# main.net
KiCad netlist of a schematic drawn in EAGLE
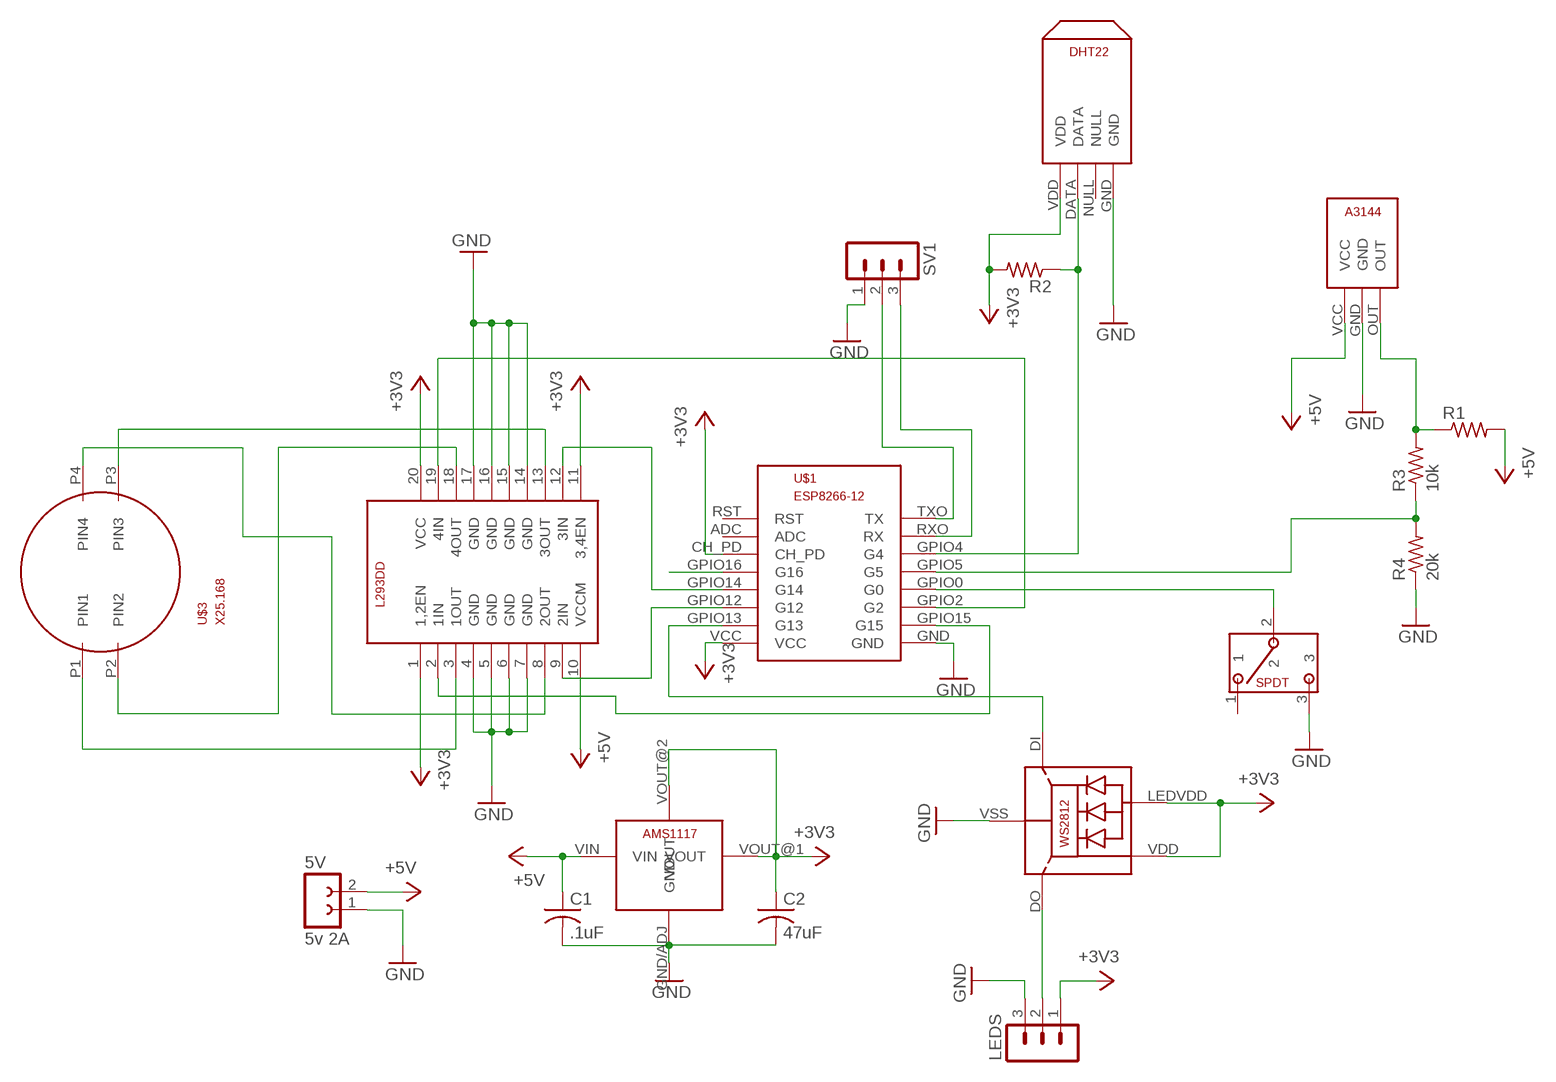
[diagram p0: schematic, sheet 1]

(export (version "E")
  (design (tool "Eeschema 10.0.6"))
  (components
    (comp (ref "5V")
      (value "5v 2A")
      (footprint "eagle-import:FE02-1")
      (libsource (lib "eagle-import") (part "FE02-1"))
    )
    (comp (ref "C1")
      (value ".1uF")
      (footprint "eagle-import:C0805")
      (libsource (lib "eagle-import") (part "C-USC0805"))
    )
    (comp (ref "C2")
      (value "47uF")
      (footprint "eagle-import:C0805")
      (libsource (lib "eagle-import") (part "C-USC0805"))
    )
    (comp (ref "LED1")
      (value "WS2812")
      (footprint "eagle-import:WS2812")
      (libsource (lib "eagle-import") (part "WS2812"))
    )
    (comp (ref "LEDS")
      (value "MA03-1")
      (footprint "eagle-import:MA03-1")
      (libsource (lib "eagle-import") (part "MA03-1"))
    )
    (comp (ref "R1")
      (value "R-US_R0805")
      (footprint "eagle-import:R0805")
      (libsource (lib "eagle-import") (part "R-US_R0805"))
    )
    (comp (ref "R2")
      (value "R-US_R0805")
      (footprint "eagle-import:R0805")
      (libsource (lib "eagle-import") (part "R-US_R0805"))
    )
    (comp (ref "R3")
      (value "10k")
      (footprint "eagle-import:R0805")
      (libsource (lib "eagle-import") (part "R-US_R0805"))
    )
    (comp (ref "R4")
      (value "20k")
      (footprint "eagle-import:R0805")
      (libsource (lib "eagle-import") (part "R-US_R0805"))
    )
    (comp (ref "SV1")
      (value "MA03-1")
      (footprint "eagle-import:MA03-1")
      (libsource (lib "eagle-import") (part "MA03-1"))
    )
    (comp (ref "U$1")
      (value "ESP12ESP12")
      (footprint "eagle-import:ESP12")
      (libsource (lib "eagle-import") (part "ESP12ESP12"))
    )
    (comp (ref "U$3")
      (value "X25.168X25.SMT")
      (footprint "eagle-import:X25-SMT")
      (libsource (lib "eagle-import") (part "X25.168X25.SMT"))
    )
    (comp (ref "U$4")
      (value "A3144")
      (footprint "eagle-import:A3144")
      (libsource (lib "eagle-import") (part "A3144"))
    )
    (comp (ref "U$5")
      (value "DH22FLAT")
      (footprint "eagle-import:DH22FLAT")
      (libsource (lib "eagle-import") (part "DH22FLAT"))
    )
    (comp (ref "U$6")
      (value "AMS11173.3V")
      (footprint "eagle-import:AMS1117")
      (libsource (lib "eagle-import") (part "AMS11173.3V"))
    )
    (comp (ref "U$7")
      (value "SMT-SPDT")
      (footprint "eagle-import:SPDT")
      (libsource (lib "eagle-import") (part "SMT-SPDT"))
    )
    (comp (ref "U$8")
      (value "L293DD")
      (footprint "eagle-import:SO20")
      (libsource (lib "eagle-import") (part "L293DD"))
    )
  )
  (nets
    (net (code "1") (name "+3V3") (class "Default")
      (node (ref "C2") (pin "1") (pinfunction "1_1") (pintype "passive"))
      (node (ref "LED1") (pin "LEDVDD") (pinfunction "LEDVDD_LEDVDD") (pintype "power_in"))
      (node (ref "LED1") (pin "VDD") (pinfunction "VDD_VDD") (pintype "power_in"))
      (node (ref "LEDS") (pin "1") (pinfunction "1_1") (pintype "passive"))
      (node (ref "R2") (pin "2") (pinfunction "2_2") (pintype "passive"))
      (node (ref "U$1") (pin "CH_PD") (pinfunction "CH_PD_CH_PD") (pintype "bidirectional"))
      (node (ref "U$1") (pin "VCC") (pinfunction "VCC_VCC") (pintype "bidirectional"))
      (node (ref "U$5") (pin "VDD") (pinfunction "VDD_VDD") (pintype "bidirectional"))
      (node (ref "U$6") (pin "VOUT@1") (pinfunction "VOUT_VOUT@1") (pintype "bidirectional"))
      (node (ref "U$6") (pin "VOUT@2") (pinfunction "VOUT_VOUT@2") (pintype "bidirectional"))
      (node (ref "U$8") (pin "1") (pinfunction "1,2EN_1") (pintype "bidirectional"))
      (node (ref "U$8") (pin "11") (pinfunction "3,4EN_11") (pintype "bidirectional"))
      (node (ref "U$8") (pin "20") (pinfunction "VCC_20") (pintype "bidirectional"))
    )
    (net (code "2") (name "+5V") (class "Default")
      (node (ref "5V") (pin "2") (pinfunction "2_2") (pintype "passive"))
      (node (ref "C1") (pin "1") (pinfunction "1_1") (pintype "passive"))
      (node (ref "R1") (pin "2") (pinfunction "2_2") (pintype "passive"))
      (node (ref "U$4") (pin "VCC") (pinfunction "VCC_VCC") (pintype "bidirectional"))
      (node (ref "U$6") (pin "VIN") (pinfunction "VIN_VIN") (pintype "bidirectional"))
      (node (ref "U$8") (pin "10") (pinfunction "VCCM_10") (pintype "bidirectional"))
    )
    (net (code "3") (name "GND") (class "Default")
      (node (ref "5V") (pin "1") (pinfunction "1_1") (pintype "passive"))
      (node (ref "C1") (pin "2") (pinfunction "2_2") (pintype "passive"))
      (node (ref "C2") (pin "2") (pinfunction "2_2") (pintype "passive"))
      (node (ref "LED1") (pin "VSS") (pinfunction "GND_VSS") (pintype "power_in"))
      (node (ref "LEDS") (pin "3") (pinfunction "3_3") (pintype "passive"))
      (node (ref "R4") (pin "1") (pinfunction "1_1") (pintype "passive"))
      (node (ref "SV1") (pin "1") (pinfunction "1_1") (pintype "passive"))
      (node (ref "U$1") (pin "GND") (pinfunction "GND_GND") (pintype "bidirectional"))
      (node (ref "U$4") (pin "GND") (pinfunction "GND_GND") (pintype "bidirectional"))
      (node (ref "U$5") (pin "GND") (pinfunction "GND_GND") (pintype "bidirectional"))
      (node (ref "U$6") (pin "GND/ADJ") (pinfunction "GND_GND/ADJ") (pintype "bidirectional"))
      (node (ref "U$7") (pin "3") (pinfunction "3_3") (pintype "bidirectional"))
      (node (ref "U$8") (pin "14") (pinfunction "GND_14") (pintype "bidirectional"))
      (node (ref "U$8") (pin "15") (pinfunction "GND_15") (pintype "bidirectional"))
      (node (ref "U$8") (pin "16") (pinfunction "GND_16") (pintype "bidirectional"))
      (node (ref "U$8") (pin "17") (pinfunction "GND_17") (pintype "bidirectional"))
      (node (ref "U$8") (pin "4") (pinfunction "GND_4") (pintype "bidirectional"))
      (node (ref "U$8") (pin "5") (pinfunction "GND_5") (pintype "bidirectional"))
      (node (ref "U$8") (pin "6") (pinfunction "GND_6") (pintype "bidirectional"))
      (node (ref "U$8") (pin "7") (pinfunction "GND_7") (pintype "bidirectional"))
    )
    (net (code "4") (name "Net-(LED1-PadDO)") (class "Default")
      (node (ref "LED1") (pin "DO") (pinfunction "DO_DO") (pintype "output"))
      (node (ref "LEDS") (pin "2") (pinfunction "2_2") (pintype "passive"))
    )
    (net (code "5") (name "Net-(R1-Pad1)") (class "Default")
      (node (ref "R1") (pin "1") (pinfunction "1_1") (pintype "passive"))
      (node (ref "R3") (pin "2") (pinfunction "2_2") (pintype "passive"))
      (node (ref "U$4") (pin "OUT") (pinfunction "OUT_OUT") (pintype "bidirectional"))
    )
    (net (code "6") (name "Net-(U$1-G0)") (class "Default")
      (node (ref "U$1") (pin "GPIO0") (pinfunction "G0_GPIO0") (pintype "bidirectional"))
      (node (ref "U$7") (pin "2") (pinfunction "2_2") (pintype "bidirectional"))
    )
    (net (code "7") (name "Net-(U$1-G2)") (class "Default")
      (node (ref "U$1") (pin "GPIO2") (pinfunction "G2_GPIO2") (pintype "bidirectional"))
      (node (ref "U$8") (pin "19") (pinfunction "4IN_19") (pintype "bidirectional"))
    )
    (net (code "8") (name "Net-(U$1-G4)") (class "Default")
      (node (ref "R2") (pin "1") (pinfunction "1_1") (pintype "passive"))
      (node (ref "U$1") (pin "GPIO4") (pinfunction "G4_GPIO4") (pintype "bidirectional"))
      (node (ref "U$5") (pin "DATA") (pinfunction "DATA_DATA") (pintype "bidirectional"))
    )
    (net (code "9") (name "Net-(U$1-G5)") (class "Default")
      (node (ref "R3") (pin "1") (pinfunction "1_1") (pintype "passive"))
      (node (ref "R4") (pin "2") (pinfunction "2_2") (pintype "passive"))
      (node (ref "U$1") (pin "GPIO5") (pinfunction "G5_GPIO5") (pintype "bidirectional"))
    )
    (net (code "10") (name "Net-(U$1-G12)") (class "Default")
      (node (ref "U$1") (pin "GPIO12") (pinfunction "G12_GPIO12") (pintype "bidirectional"))
      (node (ref "U$8") (pin "9") (pinfunction "2IN_9") (pintype "bidirectional"))
    )
    (net (code "11") (name "Net-(U$1-G13)") (class "Default")
      (node (ref "LED1") (pin "DI") (pinfunction "DI_DI") (pintype "input"))
      (node (ref "U$1") (pin "GPIO13") (pinfunction "G13_GPIO13") (pintype "bidirectional"))
    )
    (net (code "12") (name "Net-(U$1-G14)") (class "Default")
      (node (ref "U$1") (pin "GPIO14") (pinfunction "G14_GPIO14") (pintype "bidirectional"))
      (node (ref "U$8") (pin "12") (pinfunction "3IN_12") (pintype "bidirectional"))
    )
    (net (code "13") (name "Net-(U$1-G15)") (class "Default")
      (node (ref "U$1") (pin "GPIO15") (pinfunction "G15_GPIO15") (pintype "bidirectional"))
      (node (ref "U$8") (pin "2") (pinfunction "1IN_2") (pintype "bidirectional"))
    )
    (net (code "14") (name "Net-(U$1-RX)") (class "Default")
      (node (ref "SV1") (pin "3") (pinfunction "3_3") (pintype "passive"))
      (node (ref "U$1") (pin "RXO") (pinfunction "RX_RXO") (pintype "bidirectional"))
    )
    (net (code "15") (name "Net-(U$1-TX)") (class "Default")
      (node (ref "SV1") (pin "2") (pinfunction "2_2") (pintype "passive"))
      (node (ref "U$1") (pin "TXO") (pinfunction "TX_TXO") (pintype "bidirectional"))
    )
    (net (code "16") (name "Net-(U$3-PIN1)") (class "Default")
      (node (ref "U$3") (pin "P1") (pinfunction "PIN1_P1") (pintype "bidirectional"))
      (node (ref "U$8") (pin "3") (pinfunction "1OUT_3") (pintype "bidirectional"))
    )
    (net (code "17") (name "Net-(U$3-PIN2)") (class "Default")
      (node (ref "U$3") (pin "P2") (pinfunction "PIN2_P2") (pintype "bidirectional"))
      (node (ref "U$8") (pin "18") (pinfunction "4OUT_18") (pintype "bidirectional"))
    )
    (net (code "18") (name "Net-(U$3-PIN3)") (class "Default")
      (node (ref "U$3") (pin "P3") (pinfunction "PIN3_P3") (pintype "bidirectional"))
      (node (ref "U$8") (pin "13") (pinfunction "3OUT_13") (pintype "bidirectional"))
    )
    (net (code "19") (name "Net-(U$3-PIN4)") (class "Default")
      (node (ref "U$3") (pin "P4") (pinfunction "PIN4_P4") (pintype "bidirectional"))
      (node (ref "U$8") (pin "8") (pinfunction "2OUT_8") (pintype "bidirectional"))
    )
    (net (code "20") (name "unconnected-(U$1-G16-PadGPIO16)") (class "Default")
      (node (ref "U$1") (pin "GPIO16") (pinfunction "G16_GPIO16") (pintype "bidirectional"))
    )
    (net (code "21") (name "unconnected-(U$1-PadADC)") (class "Default")
      (node (ref "U$1") (pin "ADC") (pinfunction "ADC_ADC") (pintype "bidirectional"))
    )
    (net (code "22") (name "unconnected-(U$1-PadRST)") (class "Default")
      (node (ref "U$1") (pin "RST") (pinfunction "RST_RST") (pintype "bidirectional"))
    )
    (net (code "23") (name "unconnected-(U$5-PadNULL)") (class "Default")
      (node (ref "U$5") (pin "NULL") (pinfunction "NULL_NULL") (pintype "bidirectional"))
    )
    (net (code "24") (name "unconnected-(U$7-Pad1)") (class "Default")
      (node (ref "U$7") (pin "1") (pinfunction "1_1") (pintype "bidirectional"))
    )
  )
)
